# 5V_REG.net
KiCad netlist of a schematic drawn in Altium Designer
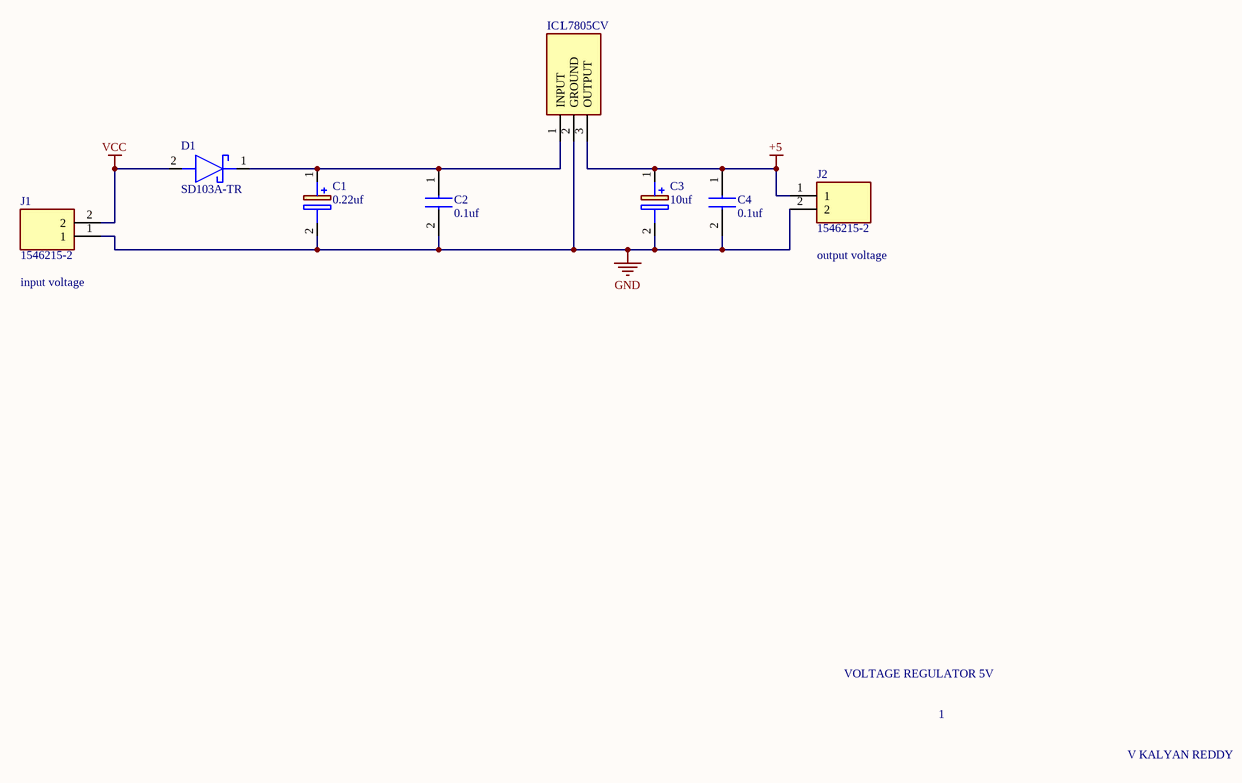
[diagram p0: 5V_REG.SchDoc]

(export (version "E")
  (design (tool "Eeschema 10.0.6"))
  (components
    (comp (ref "C1")
      (value "0.22uf")
      (footprint "SamacSys:CAPPRD200W52D500H1250")
      (description "Capacitor Polarised")
      (fields
        (field (name "MANUFACTURER_PART_NUMBER") "860010772002")
        (field (name "MOUSER PART NUMBER") "710-860010772002")
      )
      (libsource (lib "*") (part "860010772002"))
    )
    (comp (ref "C2")
      (value "0.1uf")
      (footprint "SamacSys:RDE5C1H100J0P1H03B")
      (description "Capacitor")
      (fields
        (field (name "MANUFACTURER_PART_NUMBER") "RDER71E104K0P1H03B")
        (field (name "MOUSER PART NUMBER") "81-RDER71E104K0P1H3B")
      )
      (libsource (lib "*") (part "RDER71E104K0P1H03B"))
    )
    (comp (ref "C3")
      (value "10uf")
      (footprint "SamacSys:CAPPRD200W55D500H1250")
      (description "Capacitor Polarised")
      (fields
        (field (name "MANUFACTURER_PART_NUMBER") "EEU-FR1H100")
        (field (name "MOUSER PART NUMBER") "667-EEU-FR1H100")
      )
      (libsource (lib "*") (part "EEU-FR1H100"))
    )
    (comp (ref "C4")
      (value "0.1uf")
      (footprint "SamacSys:RDE5C1H100J0P1H03B")
      (description "Capacitor")
      (fields
        (field (name "MANUFACTURER_PART_NUMBER") "RDER71E104K0P1H03B")
        (field (name "MOUSER PART NUMBER") "81-RDER71E104K0P1H3B")
      )
      (libsource (lib "*") (part "RDER71E104K0P1H03B"))
    )
    (comp (ref "D1")
      (value "SD103A-TR")
      (footprint "SamacSys:DIOAD950W60L350D150")
      (description "Schottky Diode")
      (fields (field (name "MOUSER PART NUMBER") "625-SD103A"))
      (libsource (lib "*") (part "SD103A-TR"))
    )
    (comp (ref "IC1")
      (value "L7805CV")
      (footprint "SamacSys:TO255P460X1020X2008-3P")
      (description "Integrated Circuit")
      (fields (field (name "MOUSER PART NUMBER") "511-L7805CV"))
      (libsource (lib "*") (part "L7805CV"))
    )
    (comp (ref "J1")
      (value "1546215-2")
      (footprint "SamacSys:15462152")
      (description "Connector")
      (fields (field (name "MOUSER PART NUMBER") "571-1546215-2"))
      (libsource (lib "") (part "1546215-2_1"))
    )
    (comp (ref "J2")
      (value "1546215-2")
      (footprint "SamacSys:15462152")
      (description "Connector")
      (fields (field (name "MOUSER PART NUMBER") "571-1546215-2"))
      (libsource (lib "*") (part "1546215-2"))
    )
  )
  (nets
    (net (code "1") (name "+5") (class "Default")
      (node (ref "C3") (pin "1") (pinfunction "+_1") (pintype "power_in"))
      (node (ref "C4") (pin "1") (pinfunction "1_1") (pintype "passive"))
      (node (ref "IC1") (pin "3") (pinfunction "OUTPUT_3") (pintype "passive"))
      (node (ref "J2") (pin "1") (pinfunction "1_1") (pintype "passive"))
    )
    (net (code "2") (name "GND") (class "Default")
      (node (ref "C1") (pin "2") (pinfunction "-_2") (pintype "passive"))
      (node (ref "C2") (pin "2") (pinfunction "2_2") (pintype "passive"))
      (node (ref "C3") (pin "2") (pinfunction "-_2") (pintype "power_in"))
      (node (ref "C4") (pin "2") (pinfunction "2_2") (pintype "passive"))
      (node (ref "IC1") (pin "2") (pinfunction "GROUND_2") (pintype "passive"))
      (node (ref "J1") (pin "1") (pinfunction "1_1") (pintype "passive"))
      (node (ref "J2") (pin "2") (pinfunction "2_2") (pintype "passive"))
    )
    (net (code "3") (name "Net-(C1-+)") (class "Default")
      (node (ref "C1") (pin "1") (pinfunction "+_1") (pintype "passive"))
      (node (ref "C2") (pin "1") (pinfunction "1_1") (pintype "passive"))
      (node (ref "D1") (pin "1") (pinfunction "K_1") (pintype "passive"))
      (node (ref "IC1") (pin "1") (pinfunction "INPUT_1") (pintype "passive"))
    )
    (net (code "4") (name "VCC") (class "Default")
      (node (ref "D1") (pin "2") (pinfunction "A_2") (pintype "passive"))
      (node (ref "J1") (pin "2") (pinfunction "2_2") (pintype "passive"))
    )
  )
)
